# PCBtest_2b.net
KiCad netlist of a schematic drawn in EAGLE
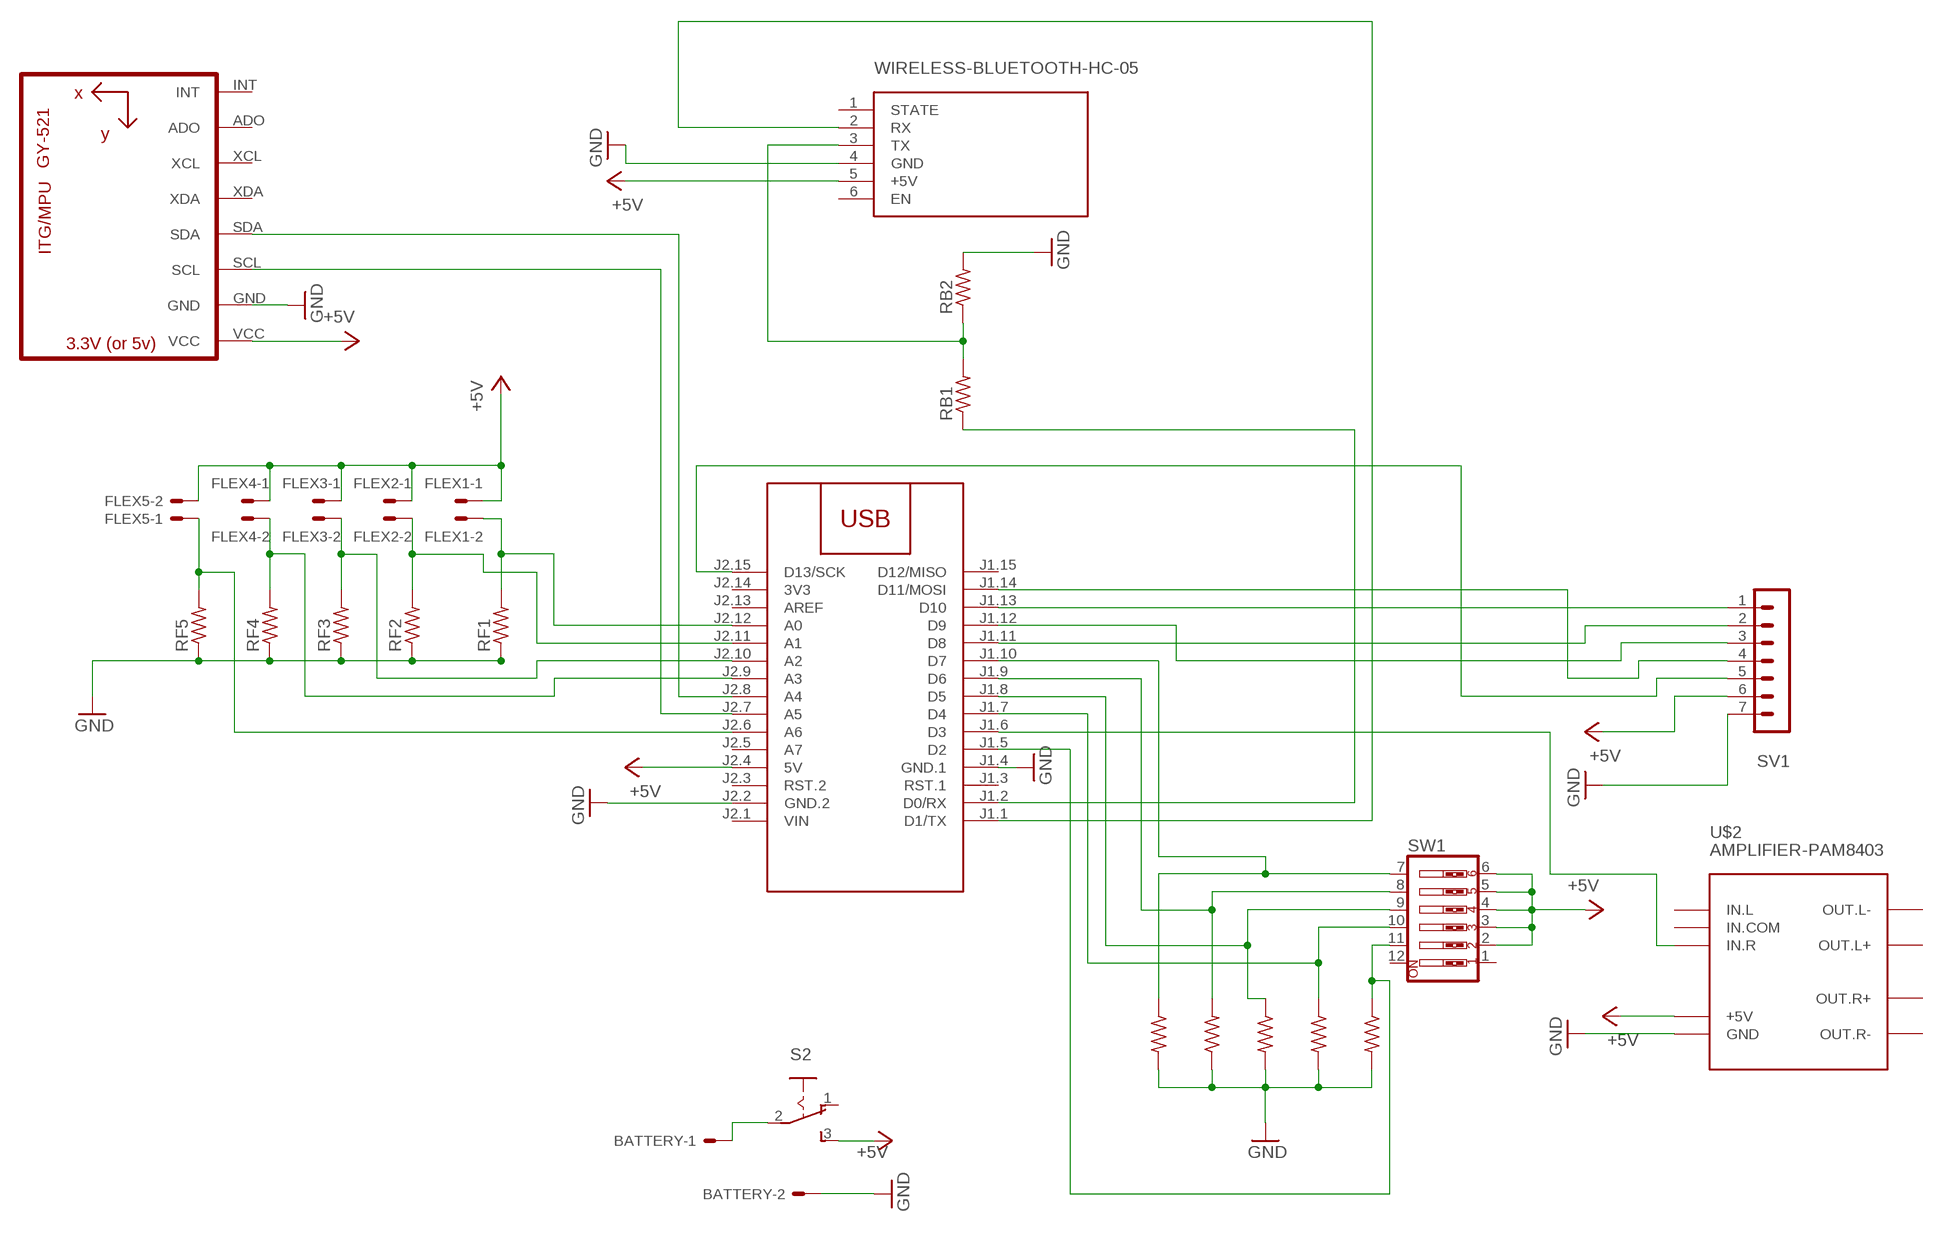
[diagram p0: schematic, sheet 1]

(export (version "E")
  (design (tool "Eeschema 10.0.6"))
  (components
    (comp (ref "BATTERY")
      (value "332-02")
      (footprint "eagle-import:332-02")
      (libsource (lib "eagle-import") (part "332-02"))
    )
    (comp (ref "FLEX1")
      (value "332-02")
      (footprint "eagle-import:332-02")
      (libsource (lib "eagle-import") (part "332-02"))
    )
    (comp (ref "FLEX2")
      (value "332-02")
      (footprint "eagle-import:332-02")
      (libsource (lib "eagle-import") (part "332-02"))
    )
    (comp (ref "FLEX3")
      (value "332-02")
      (footprint "eagle-import:332-02")
      (libsource (lib "eagle-import") (part "332-02"))
    )
    (comp (ref "FLEX4")
      (value "332-02")
      (footprint "eagle-import:332-02")
      (libsource (lib "eagle-import") (part "332-02"))
    )
    (comp (ref "FLEX5")
      (value "332-02")
      (footprint "eagle-import:332-02")
      (libsource (lib "eagle-import") (part "332-02"))
    )
    (comp (ref "M1")
      (value "ARDUINO-NANO-3.0")
      (footprint "eagle-import:ARDUINO-NANO-3.0")
      (libsource (lib "eagle-import") (part "ARDUINO-NANO-3.0"))
    )
    (comp (ref "RB1")
      (value "R-US_0204/7")
      (footprint "eagle-import:0204_7")
      (libsource (lib "eagle-import") (part "R-US_0204/7"))
    )
    (comp (ref "RB2")
      (value "R-US_0204/7")
      (footprint "eagle-import:0204_7")
      (libsource (lib "eagle-import") (part "R-US_0204/7"))
    )
    (comp (ref "RF1")
      (value "R-US_0204/7")
      (footprint "eagle-import:0204_7")
      (libsource (lib "eagle-import") (part "R-US_0204/7"))
    )
    (comp (ref "RF2")
      (value "R-US_0204/7")
      (footprint "eagle-import:0204_7")
      (libsource (lib "eagle-import") (part "R-US_0204/7"))
    )
    (comp (ref "RF3")
      (value "R-US_0204/7")
      (footprint "eagle-import:0204_7")
      (libsource (lib "eagle-import") (part "R-US_0204/7"))
    )
    (comp (ref "RF4")
      (value "R-US_0204/7")
      (footprint "eagle-import:0204_7")
      (libsource (lib "eagle-import") (part "R-US_0204/7"))
    )
    (comp (ref "RF5")
      (value "R-US_0204/7")
      (footprint "eagle-import:0204_7")
      (libsource (lib "eagle-import") (part "R-US_0204/7"))
    )
    (comp (ref "RS1")
      (value "R-US_0204/7")
      (footprint "eagle-import:0204_7")
      (libsource (lib "eagle-import") (part "R-US_0204/7"))
    )
    (comp (ref "RS2")
      (value "R-US_0204/7")
      (footprint "eagle-import:0204_7")
      (libsource (lib "eagle-import") (part "R-US_0204/7"))
    )
    (comp (ref "RS3")
      (value "R-US_0204/7")
      (footprint "eagle-import:0204_7")
      (libsource (lib "eagle-import") (part "R-US_0204/7"))
    )
    (comp (ref "RS4")
      (value "R-US_0204/7")
      (footprint "eagle-import:0204_7")
      (libsource (lib "eagle-import") (part "R-US_0204/7"))
    )
    (comp (ref "RS5")
      (value "R-US_0204/7")
      (footprint "eagle-import:0204_7")
      (libsource (lib "eagle-import") (part "R-US_0204/7"))
    )
    (comp (ref "S2")
      (value "255SB")
      (footprint "eagle-import:255SB")
      (libsource (lib "eagle-import") (part "255SB"))
    )
    (comp (ref "SV1")
      (value "MA07-1")
      (footprint "eagle-import:MA07-1")
      (libsource (lib "eagle-import") (part "MA07-1"))
    )
    (comp (ref "SW1")
      (value "SW_DIP-6")
      (footprint "eagle-import:EDG-06")
      (libsource (lib "eagle-import") (part "SW_DIP-6"))
    )
    (comp (ref "U$1")
      (value "WIRELESS-BLUETOOTH-HC-05")
      (footprint "eagle-import:WIRELESS-BLUETOOTH-HC-05")
      (libsource (lib "eagle-import") (part "WIRELESS-BLUETOOTH-HC-05"))
    )
    (comp (ref "U$2")
      (value "AMPLIFIER-PAM8403")
      (footprint "eagle-import:AMPLIFIER-PAM8403")
      (libsource (lib "eagle-import") (part "AMPLIFIER-PAM8403"))
    )
    (comp (ref "U1")
      (value "GY-521MPU6050")
      (footprint "eagle-import:GY-521")
      (libsource (lib "eagle-import") (part "GY-521MPU6050"))
    )
  )
  (nets
    (net (code "1") (name "+5V") (class "Default")
      (node (ref "FLEX1") (pin "1") (pinfunction "S_1") (pintype "passive"))
      (node (ref "FLEX2") (pin "1") (pinfunction "S_1") (pintype "passive"))
      (node (ref "FLEX3") (pin "1") (pinfunction "S_1") (pintype "passive"))
      (node (ref "FLEX4") (pin "1") (pinfunction "S_1") (pintype "passive"))
      (node (ref "FLEX5") (pin "2") (pinfunction "S_2") (pintype "passive"))
      (node (ref "M1") (pin "J2.4") (pinfunction "5V_J2.4") (pintype "power_in"))
      (node (ref "S2") (pin "3") (pinfunction "S_3") (pintype "passive"))
      (node (ref "SV1") (pin "6") (pinfunction "6_6") (pintype "passive"))
      (node (ref "SW1") (pin "2") (pinfunction "2_2") (pintype "passive"))
      (node (ref "SW1") (pin "3") (pinfunction "3_3") (pintype "passive"))
      (node (ref "SW1") (pin "4") (pinfunction "4_4") (pintype "passive"))
      (node (ref "SW1") (pin "5") (pinfunction "5_5") (pintype "passive"))
      (node (ref "SW1") (pin "6") (pinfunction "6_6") (pintype "passive"))
      (node (ref "U$1") (pin "5") (pinfunction "+5V_5") (pintype "power_in"))
      (node (ref "U$2") (pin "+5V") (pinfunction "+5V_+5V") (pintype "power_in"))
      (node (ref "U1") (pin "VCC") (pinfunction "VCC_VCC") (pintype "bidirectional"))
    )
    (net (code "2") (name "/3V3") (class "Default")
      (node (ref "M1") (pin "J2.14") (pinfunction "3V3_J2.14") (pintype "power_in"))
    )
    (net (code "3") (name "/VIN") (class "Default")
      (node (ref "M1") (pin "J2.1") (pinfunction "VIN_J2.1") (pintype "power_in"))
    )
    (net (code "4") (name "GND") (class "Default")
      (node (ref "BATTERY") (pin "2") (pinfunction "S_2") (pintype "passive"))
      (node (ref "M1") (pin "J1.4") (pinfunction "GND.1_J1.4") (pintype "power_in"))
      (node (ref "M1") (pin "J2.2") (pinfunction "GND.2_J2.2") (pintype "power_in"))
      (node (ref "RB2") (pin "2") (pinfunction "2_2") (pintype "passive"))
      (node (ref "RF1") (pin "1") (pinfunction "1_1") (pintype "passive"))
      (node (ref "RF2") (pin "1") (pinfunction "1_1") (pintype "passive"))
      (node (ref "RF3") (pin "1") (pinfunction "1_1") (pintype "passive"))
      (node (ref "RF4") (pin "1") (pinfunction "1_1") (pintype "passive"))
      (node (ref "RF5") (pin "1") (pinfunction "1_1") (pintype "passive"))
      (node (ref "RS1") (pin "2") (pinfunction "2_2") (pintype "passive"))
      (node (ref "RS2") (pin "2") (pinfunction "2_2") (pintype "passive"))
      (node (ref "RS3") (pin "2") (pinfunction "2_2") (pintype "passive"))
      (node (ref "RS4") (pin "1") (pinfunction "1_1") (pintype "passive"))
      (node (ref "RS5") (pin "2") (pinfunction "2_2") (pintype "passive"))
      (node (ref "SV1") (pin "7") (pinfunction "7_7") (pintype "passive"))
      (node (ref "U$1") (pin "4") (pinfunction "GND_4") (pintype "power_in"))
      (node (ref "U$2") (pin "GND") (pinfunction "GND_GND") (pintype "power_in"))
      (node (ref "U1") (pin "GND") (pinfunction "GND_GND") (pintype "bidirectional"))
    )
    (net (code "5") (name "Net-(BATTERYA-S)") (class "Default")
      (node (ref "BATTERY") (pin "1") (pinfunction "S_1") (pintype "passive"))
      (node (ref "S2") (pin "2") (pinfunction "P_2") (pintype "passive"))
    )
    (net (code "6") (name "Net-(FLEX1B-S)") (class "Default")
      (node (ref "FLEX1") (pin "2") (pinfunction "S_2") (pintype "passive"))
      (node (ref "M1") (pin "J2.12") (pinfunction "A0_J2.12") (pintype "bidirectional"))
      (node (ref "RF1") (pin "2") (pinfunction "2_2") (pintype "passive"))
    )
    (net (code "7") (name "Net-(FLEX2B-S)") (class "Default")
      (node (ref "FLEX2") (pin "2") (pinfunction "S_2") (pintype "passive"))
      (node (ref "M1") (pin "J2.11") (pinfunction "A1_J2.11") (pintype "bidirectional"))
      (node (ref "RF2") (pin "2") (pinfunction "2_2") (pintype "passive"))
    )
    (net (code "8") (name "Net-(FLEX3B-S)") (class "Default")
      (node (ref "FLEX3") (pin "2") (pinfunction "S_2") (pintype "passive"))
      (node (ref "M1") (pin "J2.10") (pinfunction "A2_J2.10") (pintype "bidirectional"))
      (node (ref "RF3") (pin "2") (pinfunction "2_2") (pintype "passive"))
    )
    (net (code "9") (name "Net-(FLEX4B-S)") (class "Default")
      (node (ref "FLEX4") (pin "2") (pinfunction "S_2") (pintype "passive"))
      (node (ref "M1") (pin "J2.9") (pinfunction "A3_J2.9") (pintype "bidirectional"))
      (node (ref "RF4") (pin "2") (pinfunction "2_2") (pintype "passive"))
    )
    (net (code "10") (name "Net-(FLEX5A-S)") (class "Default")
      (node (ref "FLEX5") (pin "1") (pinfunction "S_1") (pintype "passive"))
      (node (ref "M1") (pin "J2.6") (pinfunction "A6_J2.6") (pintype "bidirectional"))
      (node (ref "RF5") (pin "2") (pinfunction "2_2") (pintype "passive"))
    )
    (net (code "11") (name "Net-(M1-A4)") (class "Default")
      (node (ref "M1") (pin "J2.8") (pinfunction "A4_J2.8") (pintype "bidirectional"))
      (node (ref "U1") (pin "SDA") (pinfunction "SDA_SDA") (pintype "bidirectional"))
    )
    (net (code "12") (name "Net-(M1-A5)") (class "Default")
      (node (ref "M1") (pin "J2.7") (pinfunction "A5_J2.7") (pintype "bidirectional"))
      (node (ref "U1") (pin "SCL") (pinfunction "SCL_SCL") (pintype "bidirectional"))
    )
    (net (code "13") (name "Net-(M1-D0{slash}RX)") (class "Default")
      (node (ref "M1") (pin "J1.2") (pinfunction "D0/RX_J1.2") (pintype "bidirectional"))
      (node (ref "RB1") (pin "1") (pinfunction "1_1") (pintype "passive"))
    )
    (net (code "14") (name "Net-(M1-D1{slash}TX)") (class "Default")
      (node (ref "M1") (pin "J1.1") (pinfunction "D1/TX_J1.1") (pintype "bidirectional"))
      (node (ref "U$1") (pin "2") (pinfunction "RX_2") (pintype "bidirectional"))
    )
    (net (code "15") (name "Net-(M1-D2)") (class "Default")
      (node (ref "M1") (pin "J1.5") (pinfunction "D2_J1.5") (pintype "bidirectional"))
      (node (ref "RS1") (pin "1") (pinfunction "1_1") (pintype "passive"))
      (node (ref "SW1") (pin "11") (pinfunction "11_11") (pintype "passive"))
    )
    (net (code "16") (name "Net-(M1-D3)") (class "Default")
      (node (ref "M1") (pin "J1.6") (pinfunction "D3_J1.6") (pintype "bidirectional"))
      (node (ref "U$2") (pin "IN.R") (pinfunction "IN.R_IN.R") (pintype "bidirectional"))
    )
    (net (code "17") (name "Net-(M1-D4)") (class "Default")
      (node (ref "M1") (pin "J1.7") (pinfunction "D4_J1.7") (pintype "bidirectional"))
      (node (ref "RS2") (pin "1") (pinfunction "1_1") (pintype "passive"))
      (node (ref "SW1") (pin "10") (pinfunction "10_10") (pintype "passive"))
    )
    (net (code "18") (name "Net-(M1-D5)") (class "Default")
      (node (ref "M1") (pin "J1.8") (pinfunction "D5_J1.8") (pintype "bidirectional"))
      (node (ref "RS3") (pin "1") (pinfunction "1_1") (pintype "passive"))
      (node (ref "SW1") (pin "9") (pinfunction "9_9") (pintype "passive"))
    )
    (net (code "19") (name "Net-(M1-D6)") (class "Default")
      (node (ref "M1") (pin "J1.9") (pinfunction "D6_J1.9") (pintype "bidirectional"))
      (node (ref "RS4") (pin "2") (pinfunction "2_2") (pintype "passive"))
      (node (ref "SW1") (pin "8") (pinfunction "8_8") (pintype "passive"))
    )
    (net (code "20") (name "Net-(M1-D7)") (class "Default")
      (node (ref "M1") (pin "J1.10") (pinfunction "D7_J1.10") (pintype "bidirectional"))
      (node (ref "RS5") (pin "1") (pinfunction "1_1") (pintype "passive"))
      (node (ref "SW1") (pin "7") (pinfunction "7_7") (pintype "passive"))
    )
    (net (code "21") (name "Net-(M1-D8)") (class "Default")
      (node (ref "M1") (pin "J1.11") (pinfunction "D8_J1.11") (pintype "bidirectional"))
      (node (ref "SV1") (pin "2") (pinfunction "2_2") (pintype "passive"))
    )
    (net (code "22") (name "Net-(M1-D9)") (class "Default")
      (node (ref "M1") (pin "J1.12") (pinfunction "D9_J1.12") (pintype "bidirectional"))
      (node (ref "SV1") (pin "3") (pinfunction "3_3") (pintype "passive"))
    )
    (net (code "23") (name "Net-(M1-D10)") (class "Default")
      (node (ref "M1") (pin "J1.13") (pinfunction "D10_J1.13") (pintype "bidirectional"))
      (node (ref "SV1") (pin "1") (pinfunction "1_1") (pintype "passive"))
    )
    (net (code "24") (name "Net-(M1-D11{slash}MOSI)") (class "Default")
      (node (ref "M1") (pin "J1.14") (pinfunction "D11/MOSI_J1.14") (pintype "bidirectional"))
      (node (ref "SV1") (pin "4") (pinfunction "4_4") (pintype "passive"))
    )
    (net (code "25") (name "Net-(M1-D13{slash}SCK)") (class "Default")
      (node (ref "M1") (pin "J2.15") (pinfunction "D13/SCK_J2.15") (pintype "bidirectional"))
      (node (ref "SV1") (pin "5") (pinfunction "5_5") (pintype "passive"))
    )
    (net (code "26") (name "Net-(U$1-TX)") (class "Default")
      (node (ref "RB1") (pin "2") (pinfunction "2_2") (pintype "passive"))
      (node (ref "RB2") (pin "1") (pinfunction "1_1") (pintype "passive"))
      (node (ref "U$1") (pin "3") (pinfunction "TX_3") (pintype "bidirectional"))
    )
    (net (code "27") (name "unconnected-(M1-A7-PadJ2.5)") (class "Default")
      (node (ref "M1") (pin "J2.5") (pinfunction "A7_J2.5") (pintype "bidirectional"))
    )
    (net (code "28") (name "unconnected-(M1-AREF-PadJ2.13)") (class "Default")
      (node (ref "M1") (pin "J2.13") (pinfunction "AREF_J2.13") (pintype "bidirectional"))
    )
    (net (code "29") (name "unconnected-(M1-D12{slash}MISO-PadJ1.15)") (class "Default")
      (node (ref "M1") (pin "J1.15") (pinfunction "D12/MISO_J1.15") (pintype "bidirectional"))
    )
    (net (code "30") (name "unconnected-(M1-RST.1-PadJ1.3)") (class "Default")
      (node (ref "M1") (pin "J1.3") (pinfunction "RST.1_J1.3") (pintype "bidirectional"))
    )
    (net (code "31") (name "unconnected-(M1-RST.2-PadJ2.3)") (class "Default")
      (node (ref "M1") (pin "J2.3") (pinfunction "RST.2_J2.3") (pintype "bidirectional"))
    )
    (net (code "32") (name "unconnected-(S2-O-Pad1)") (class "Default")
      (node (ref "S2") (pin "1") (pinfunction "O_1") (pintype "passive"))
    )
    (net (code "33") (name "unconnected-(SW1-Pad1)") (class "Default")
      (node (ref "SW1") (pin "1") (pinfunction "1_1") (pintype "passive"))
    )
    (net (code "34") (name "unconnected-(SW1-Pad12)") (class "Default")
      (node (ref "SW1") (pin "12") (pinfunction "12_12") (pintype "passive"))
    )
    (net (code "35") (name "unconnected-(U$1-EN-Pad6)") (class "Default")
      (node (ref "U$1") (pin "6") (pinfunction "EN_6") (pintype "bidirectional"))
    )
    (net (code "36") (name "unconnected-(U$1-STATE-Pad1)") (class "Default")
      (node (ref "U$1") (pin "1") (pinfunction "STATE_1") (pintype "bidirectional"))
    )
    (net (code "37") (name "unconnected-(U$2-PadIN.COM)") (class "Default")
      (node (ref "U$2") (pin "IN.COM") (pinfunction "IN.COM_IN.COM") (pintype "input"))
    )
    (net (code "38") (name "unconnected-(U$2-PadIN.L)") (class "Default")
      (node (ref "U$2") (pin "IN.L") (pinfunction "IN.L_IN.L") (pintype "input"))
    )
    (net (code "39") (name "unconnected-(U$2-PadOUT.L+)") (class "Default")
      (node (ref "U$2") (pin "OUT.L+") (pinfunction "OUT.L+_OUT.L+") (pintype "output"))
    )
    (net (code "40") (name "unconnected-(U$2-PadOUT.L-)") (class "Default")
      (node (ref "U$2") (pin "OUT.L-") (pinfunction "OUT.L-_OUT.L-") (pintype "output"))
    )
    (net (code "41") (name "unconnected-(U$2-PadOUT.R+)") (class "Default")
      (node (ref "U$2") (pin "OUT.R+") (pinfunction "OUT.R+_OUT.R+") (pintype "output"))
    )
    (net (code "42") (name "unconnected-(U$2-PadOUT.R-)") (class "Default")
      (node (ref "U$2") (pin "OUT.R-") (pinfunction "OUT.R-_OUT.R-") (pintype "output"))
    )
    (net (code "43") (name "unconnected-(U1-PadADO)") (class "Default")
      (node (ref "U1") (pin "ADO") (pinfunction "ADO_ADO") (pintype "bidirectional"))
    )
    (net (code "44") (name "unconnected-(U1-PadINT)") (class "Default")
      (node (ref "U1") (pin "INT") (pinfunction "INT_INT") (pintype "bidirectional"))
    )
    (net (code "45") (name "unconnected-(U1-PadXCL)") (class "Default")
      (node (ref "U1") (pin "XCL") (pinfunction "XCL_XCL") (pintype "bidirectional"))
    )
    (net (code "46") (name "unconnected-(U1-PadXDA)") (class "Default")
      (node (ref "U1") (pin "XDA") (pinfunction "XDA_XDA") (pintype "bidirectional"))
    )
  )
)
